# HIDaspx_mini2.net
KiCad netlist of a schematic drawn in EAGLE
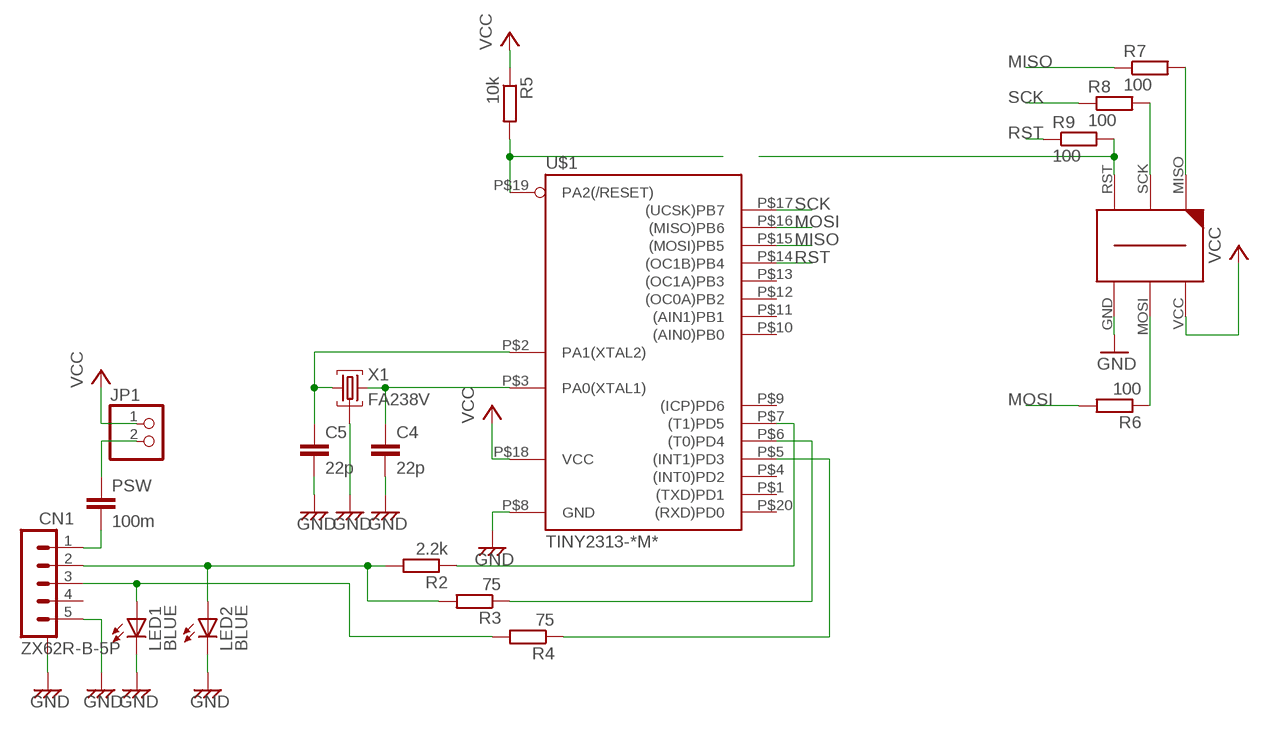
[diagram p0: schematic, sheet 1]

(export (version "E")
  (design (tool "Eeschema 10.0.6"))
  (components
    (comp (ref "C4")
      (value "22p")
      (footprint "eagle-import:C0603")
      (libsource (lib "eagle-import") (part "C-EUC0603"))
    )
    (comp (ref "C5")
      (value "22p")
      (footprint "eagle-import:C0603")
      (libsource (lib "eagle-import") (part "C-EUC0603"))
    )
    (comp (ref "CN1")
      (value "ZX62R-B-5P")
      (footprint "eagle-import:MICRO-B")
      (libsource (lib "eagle-import") (part "ZX62R-B-5P"))
    )
    (comp (ref "JP1")
      (value "PINHD-1X2HALF")
      (footprint "eagle-import:1X02_HALF")
      (libsource (lib "eagle-import") (part "PINHD-1X2HALF"))
    )
    (comp (ref "LED1")
      (value "BLUE")
      (footprint "eagle-import:SML0603")
      (libsource (lib "eagle-import") (part "LEDSML0603"))
    )
    (comp (ref "LED2")
      (value "BLUE")
      (footprint "eagle-import:SML0603")
      (libsource (lib "eagle-import") (part "LEDSML0603"))
    )
    (comp (ref "PSW")
      (value "100m")
      (footprint "eagle-import:C3225")
      (libsource (lib "eagle-import") (part "C-EUC3225"))
    )
    (comp (ref "R2")
      (value "2.2k")
      (footprint "eagle-import:R0603")
      (libsource (lib "eagle-import") (part "R-EU_R0603"))
    )
    (comp (ref "R3")
      (value "75")
      (footprint "eagle-import:R0603")
      (libsource (lib "eagle-import") (part "R-EU_R0603"))
    )
    (comp (ref "R4")
      (value "75")
      (footprint "eagle-import:R0603")
      (libsource (lib "eagle-import") (part "R-EU_R0603"))
    )
    (comp (ref "R5")
      (value "10k")
      (footprint "eagle-import:R0603")
      (libsource (lib "eagle-import") (part "R-EU_R0603"))
    )
    (comp (ref "R6")
      (value "100")
      (footprint "eagle-import:R0603")
      (libsource (lib "eagle-import") (part "R-EU_R0603"))
    )
    (comp (ref "R7")
      (value "100")
      (footprint "eagle-import:R0603")
      (libsource (lib "eagle-import") (part "R-EU_R0603"))
    )
    (comp (ref "R8")
      (value "100")
      (footprint "eagle-import:R0603")
      (libsource (lib "eagle-import") (part "R-EU_R0603"))
    )
    (comp (ref "R9")
      (value "100")
      (footprint "eagle-import:R0603")
      (libsource (lib "eagle-import") (part "R-EU_R0603"))
    )
    (comp (ref "U$1")
      (value "TINY2313-*M*")
      (footprint "eagle-import:MLF20")
      (libsource (lib "eagle-import") (part "TINY2313-M"))
    )
    (comp (ref "U$2")
      (value "AVR-ISP-6-EDGE")
      (footprint "eagle-import:6PAD_ISP")
      (libsource (lib "eagle-import") (part "AVR-ISP-6-EDGE"))
    )
    (comp (ref "X1")
      (value "FA238V")
      (footprint "eagle-import:V66RA")
      (libsource (lib "eagle-import") (part "FA238V"))
    )
  )
  (nets
    (net (code "1") (name "/MISO") (class "Default")
      (node (ref "R7") (pin "1") (pinfunction "1_1") (pintype "passive"))
      (node (ref "U$1") (pin "P$15") (pinfunction "(MOSI)PB5_P$15") (pintype "bidirectional"))
    )
    (net (code "2") (name "/MOSI") (class "Default")
      (node (ref "R6") (pin "2") (pinfunction "2_2") (pintype "passive"))
      (node (ref "U$1") (pin "P$16") (pinfunction "(MISO)PB6_P$16") (pintype "bidirectional"))
    )
    (net (code "3") (name "/RST") (class "Default")
      (node (ref "R9") (pin "1") (pinfunction "1_1") (pintype "passive"))
      (node (ref "U$1") (pin "P$14") (pinfunction "(OC1B)PB4_P$14") (pintype "bidirectional"))
    )
    (net (code "4") (name "/SCK") (class "Default")
      (node (ref "R8") (pin "1") (pinfunction "1_1") (pintype "passive"))
      (node (ref "U$1") (pin "P$17") (pinfunction "(UCSK)PB7_P$17") (pintype "bidirectional"))
    )
    (net (code "5") (name "GND") (class "Default")
      (node (ref "C4") (pin "2") (pinfunction "2_2") (pintype "passive"))
      (node (ref "C5") (pin "2") (pinfunction "2_2") (pintype "passive"))
      (node (ref "CN1") (pin "5") (pinfunction "1.VBUS_5") (pintype "passive"))
      (node (ref "CN1") (pin "CASE@1") (pinfunction "P$1_CASE@1") (pintype "bidirectional"))
      (node (ref "CN1") (pin "CASE@2") (pinfunction "P$1_CASE@2") (pintype "bidirectional"))
      (node (ref "CN1") (pin "CASE@3") (pinfunction "P$1_CASE@3") (pintype "bidirectional"))
      (node (ref "CN1") (pin "CASE@4") (pinfunction "P$1_CASE@4") (pintype "bidirectional"))
      (node (ref "LED1") (pin "C") (pinfunction "C_C") (pintype "passive"))
      (node (ref "LED2") (pin "C") (pinfunction "C_C") (pintype "passive"))
      (node (ref "U$1") (pin "P$8") (pinfunction "GND_P$8") (pintype "power_in"))
      (node (ref "U$2") (pin "GND") (pinfunction "P$4_GND") (pintype "bidirectional"))
      (node (ref "X1") (pin "P2GND") (pinfunction "GND_P2GND") (pintype "bidirectional"))
      (node (ref "X1") (pin "P4GND") (pinfunction "GND_P4GND") (pintype "bidirectional"))
    )
    (net (code "6") (name "Net-(CN1-3.D+)") (class "Default")
      (node (ref "CN1") (pin "3") (pinfunction "3.D+_3") (pintype "passive"))
      (node (ref "LED1") (pin "A") (pinfunction "A_A") (pintype "passive"))
      (node (ref "R4") (pin "2") (pinfunction "2_2") (pintype "passive"))
    )
    (net (code "7") (name "Net-(CN1-4.ID)") (class "Default")
      (node (ref "CN1") (pin "2") (pinfunction "4.ID_2") (pintype "passive"))
      (node (ref "LED2") (pin "A") (pinfunction "A_A") (pintype "passive"))
      (node (ref "R2") (pin "2") (pinfunction "2_2") (pintype "passive"))
      (node (ref "R3") (pin "2") (pinfunction "2_2") (pintype "passive"))
    )
    (net (code "8") (name "Net-(CN1-5.GND)") (class "Default")
      (node (ref "CN1") (pin "1") (pinfunction "5.GND_1") (pintype "passive"))
      (node (ref "PSW") (pin "2") (pinfunction "2_2") (pintype "passive"))
    )
    (net (code "9") (name "Net-(JP1-Pad2)") (class "Default")
      (node (ref "JP1") (pin "2") (pinfunction "2_2") (pintype "passive"))
      (node (ref "PSW") (pin "1") (pinfunction "1_1") (pintype "passive"))
    )
    (net (code "10") (name "Net-(U$1-(INT1)PD3)") (class "Default")
      (node (ref "R4") (pin "1") (pinfunction "1_1") (pintype "passive"))
      (node (ref "U$1") (pin "P$5") (pinfunction "(INT1)PD3_P$5") (pintype "bidirectional"))
    )
    (net (code "11") (name "Net-(U$1-(T0)PD4)") (class "Default")
      (node (ref "R3") (pin "1") (pinfunction "1_1") (pintype "passive"))
      (node (ref "U$1") (pin "P$6") (pinfunction "(T0)PD4_P$6") (pintype "bidirectional"))
    )
    (net (code "12") (name "Net-(U$1-(T1)PD5)") (class "Default")
      (node (ref "R2") (pin "1") (pinfunction "1_1") (pintype "passive"))
      (node (ref "U$1") (pin "P$7") (pinfunction "(T1)PD5_P$7") (pintype "bidirectional"))
    )
    (net (code "13") (name "Net-(U$1-PA0(XTAL1))") (class "Default")
      (node (ref "C4") (pin "1") (pinfunction "1_1") (pintype "passive"))
      (node (ref "U$1") (pin "P$3") (pinfunction "PA0(XTAL1)_P$3") (pintype "bidirectional"))
      (node (ref "X1") (pin "P3X2") (pinfunction "X2_P3X2") (pintype "output"))
    )
    (net (code "14") (name "Net-(U$1-PA1(XTAL2))") (class "Default")
      (node (ref "C5") (pin "1") (pinfunction "1_1") (pintype "passive"))
      (node (ref "U$1") (pin "P$2") (pinfunction "PA1(XTAL2)_P$2") (pintype "bidirectional"))
      (node (ref "X1") (pin "P1X1") (pinfunction "X1_P1X1") (pintype "output"))
    )
    (net (code "15") (name "Net-(U$1-PA2({slash}RESET))") (class "Default")
      (node (ref "R5") (pin "2") (pinfunction "2_2") (pintype "passive"))
      (node (ref "U$1") (pin "P$19") (pinfunction "PA2(/RESET)_P$19") (pintype "input"))
    )
    (net (code "16") (name "Net-(U$2-P$1)") (class "Default")
      (node (ref "R7") (pin "2") (pinfunction "2_2") (pintype "passive"))
      (node (ref "U$2") (pin "MISO") (pinfunction "P$1_MISO") (pintype "bidirectional"))
    )
    (net (code "17") (name "Net-(U$2-P$2)") (class "Default")
      (node (ref "R8") (pin "2") (pinfunction "2_2") (pintype "passive"))
      (node (ref "U$2") (pin "SCK") (pinfunction "P$2_SCK") (pintype "bidirectional"))
    )
    (net (code "18") (name "Net-(U$2-P$3)") (class "Default")
      (node (ref "R9") (pin "2") (pinfunction "2_2") (pintype "passive"))
      (node (ref "U$2") (pin "RST") (pinfunction "P$3_RST") (pintype "bidirectional"))
    )
    (net (code "19") (name "Net-(U$2-P$5)") (class "Default")
      (node (ref "R6") (pin "1") (pinfunction "1_1") (pintype "passive"))
      (node (ref "U$2") (pin "MOSI") (pinfunction "P$5_MOSI") (pintype "bidirectional"))
    )
    (net (code "20") (name "VCC") (class "Default")
      (node (ref "JP1") (pin "1") (pinfunction "1_1") (pintype "passive"))
      (node (ref "R5") (pin "1") (pinfunction "1_1") (pintype "passive"))
      (node (ref "U$1") (pin "P$18") (pinfunction "VCC_P$18") (pintype "power_in"))
      (node (ref "U$2") (pin "VCC") (pinfunction "P$6_VCC") (pintype "bidirectional"))
    )
    (net (code "21") (name "unconnected-(CN1-2.D--Pad4)") (class "Default")
      (node (ref "CN1") (pin "4") (pinfunction "2.D-_4") (pintype "passive"))
    )
    (net (code "22") (name "unconnected-(U$1-(AIN0)PB0-PadP$10)") (class "Default")
      (node (ref "U$1") (pin "P$10") (pinfunction "(AIN0)PB0_P$10") (pintype "bidirectional"))
    )
    (net (code "23") (name "unconnected-(U$1-(AIN1)PB1-PadP$11)") (class "Default")
      (node (ref "U$1") (pin "P$11") (pinfunction "(AIN1)PB1_P$11") (pintype "bidirectional"))
    )
    (net (code "24") (name "unconnected-(U$1-(ICP)PD6-PadP$9)") (class "Default")
      (node (ref "U$1") (pin "P$9") (pinfunction "(ICP)PD6_P$9") (pintype "bidirectional"))
    )
    (net (code "25") (name "unconnected-(U$1-(INT0)PD2-PadP$4)") (class "Default")
      (node (ref "U$1") (pin "P$4") (pinfunction "(INT0)PD2_P$4") (pintype "bidirectional"))
    )
    (net (code "26") (name "unconnected-(U$1-(OC0A)PB2-PadP$12)") (class "Default")
      (node (ref "U$1") (pin "P$12") (pinfunction "(OC0A)PB2_P$12") (pintype "bidirectional"))
    )
    (net (code "27") (name "unconnected-(U$1-(OC1A)PB3-PadP$13)") (class "Default")
      (node (ref "U$1") (pin "P$13") (pinfunction "(OC1A)PB3_P$13") (pintype "bidirectional"))
    )
    (net (code "28") (name "unconnected-(U$1-(RXD)PD0-PadP$20)") (class "Default")
      (node (ref "U$1") (pin "P$20") (pinfunction "(RXD)PD0_P$20") (pintype "bidirectional"))
    )
    (net (code "29") (name "unconnected-(U$1-(TXD)PD1-PadP$1)") (class "Default")
      (node (ref "U$1") (pin "P$1") (pinfunction "(TXD)PD1_P$1") (pintype "bidirectional"))
    )
  )
)
